# QSPI-Breakout.net
KiCad netlist of a schematic drawn in EAGLE
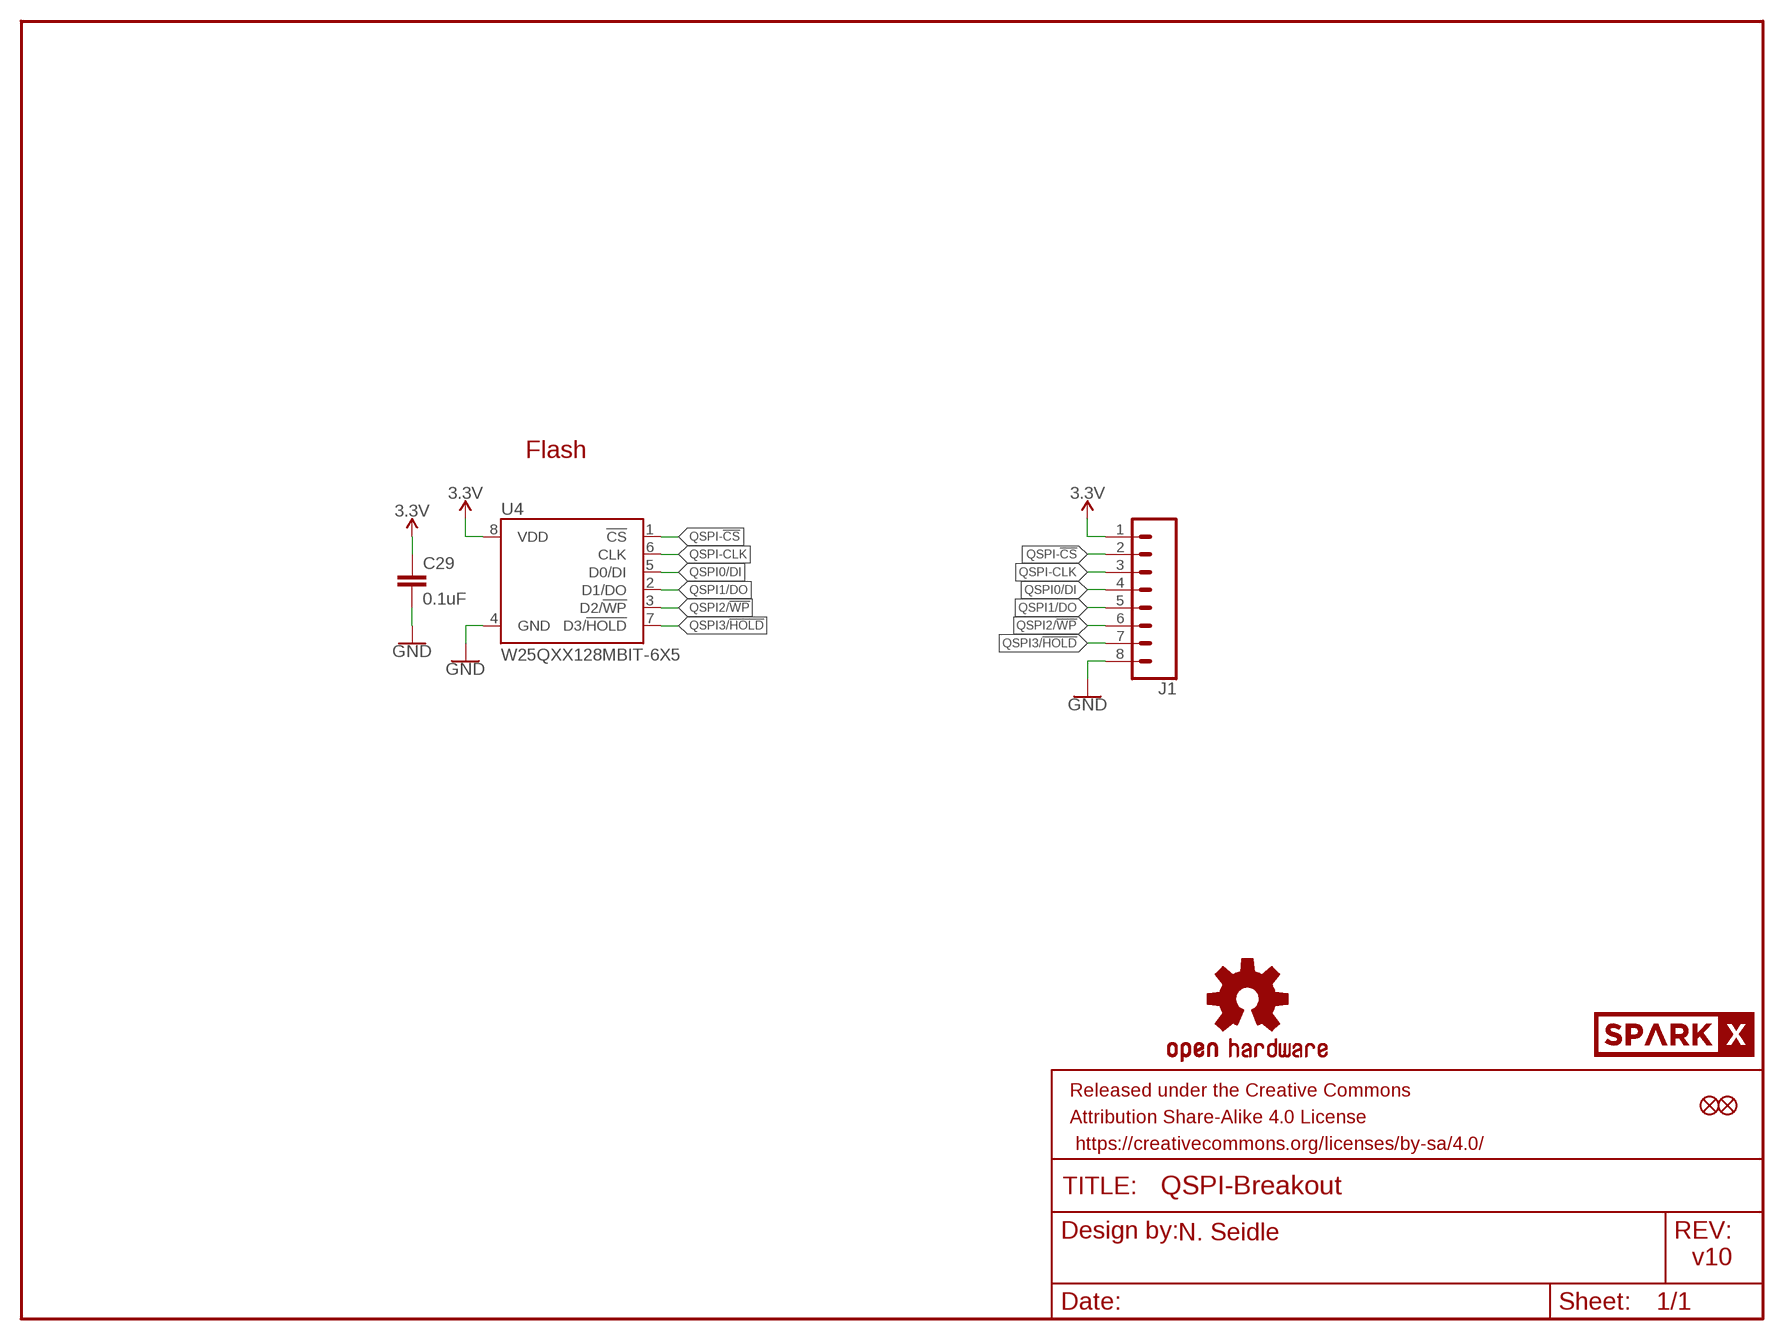
[diagram p0: schematic, sheet 1]

(export (version "E")
  (design (tool "Eeschema 10.0.6"))
  (components
    (comp (ref "C29")
      (value "0.1uF")
      (footprint "eagle-import:0603")
      (libsource (lib "eagle-import") (part "0.1UF-0603-25V-(+80/-20%)"))
    )
    (comp (ref "FD1")
      (value "FIDUCIALUFIDUCIAL")
      (footprint "eagle-import:FIDUCIAL-MICRO")
      (libsource (lib "eagle-import") (part "FIDUCIALUFIDUCIAL"))
    )
    (comp (ref "FD2")
      (value "FIDUCIALUFIDUCIAL")
      (footprint "eagle-import:FIDUCIAL-MICRO")
      (libsource (lib "eagle-import") (part "FIDUCIALUFIDUCIAL"))
    )
    (comp (ref "FRAME2")
      (value "FRAME-LETTER")
      (footprint "eagle-import:CREATIVE_COMMONS")
      (libsource (lib "eagle-import") (part "FRAME-LETTER"))
    )
    (comp (ref "J1")
      (value "CONN_08NO_SILK_DNP")
      (footprint "eagle-import:1X08_NO_SILK")
      (libsource (lib "eagle-import") (part "CONN_08NO_SILK_DNP"))
    )
    (comp (ref "LOGO2")
      (value "OSHW-LOGONO_SILK")
      (footprint "eagle-import:DUMMY")
      (libsource (lib "eagle-import") (part "OSHW-LOGONO_SILK"))
    )
    (comp (ref "U$3")
      (value "SPARKX-LOGO4")
      (footprint "eagle-import:SPARKX-MEDIUM")
      (libsource (lib "eagle-import") (part "SPARKX-LOGO4"))
    )
    (comp (ref "U4")
      (value "W25QXX128MBIT-6X5")
      (footprint "eagle-import:WSON-8-6X5-SKINNY_CENTERPAD")
      (libsource (lib "eagle-import") (part "W25QXX128MBIT-6X5-SKINNY_CENTER"))
    )
  )
  (nets
    (net (code "1") (name "/QSPI-~{CS}") (class "Default")
      (node (ref "J1") (pin "2") (pinfunction "2_2") (pintype "passive"))
      (node (ref "U4") (pin "1") (pinfunction "~{CS}_1") (pintype "bidirectional"))
    )
    (net (code "2") (name "/QSPI2{slash}~{WP}") (class "Default")
      (node (ref "J1") (pin "6") (pinfunction "6_6") (pintype "passive"))
      (node (ref "U4") (pin "3") (pinfunction "D2/~{WP}_3") (pintype "bidirectional"))
    )
    (net (code "3") (name "/QSPI3{slash}~{HOLD}") (class "Default")
      (node (ref "J1") (pin "7") (pinfunction "7_7") (pintype "passive"))
      (node (ref "U4") (pin "7") (pinfunction "D3/~{HOLD}_7") (pintype "bidirectional"))
    )
    (net (code "4") (name "3.3V") (class "Default")
      (node (ref "C29") (pin "1") (pinfunction "1_1") (pintype "passive"))
      (node (ref "J1") (pin "1") (pinfunction "1_1") (pintype "passive"))
      (node (ref "U4") (pin "8") (pinfunction "VDD_8") (pintype "bidirectional"))
    )
    (net (code "5") (name "GND") (class "Default")
      (node (ref "C29") (pin "2") (pinfunction "2_2") (pintype "passive"))
      (node (ref "J1") (pin "8") (pinfunction "8_8") (pintype "passive"))
      (node (ref "U4") (pin "4") (pinfunction "GND_4") (pintype "bidirectional"))
    )
    (net (code "6") (name "QSPI-CLK") (class "Default")
      (node (ref "J1") (pin "3") (pinfunction "3_3") (pintype "passive"))
      (node (ref "U4") (pin "6") (pinfunction "CLK_6") (pintype "bidirectional"))
    )
    (net (code "7") (name "QSPI0{slash}DI") (class "Default")
      (node (ref "J1") (pin "4") (pinfunction "4_4") (pintype "passive"))
      (node (ref "U4") (pin "5") (pinfunction "D0/DI_5") (pintype "bidirectional"))
    )
    (net (code "8") (name "QSPI1{slash}DO") (class "Default")
      (node (ref "J1") (pin "5") (pinfunction "5_5") (pintype "passive"))
      (node (ref "U4") (pin "2") (pinfunction "D1/DO_2") (pintype "bidirectional"))
    )
  )
)
